# schematic.net
KiCad netlist of a schematic drawn in Altium Designer
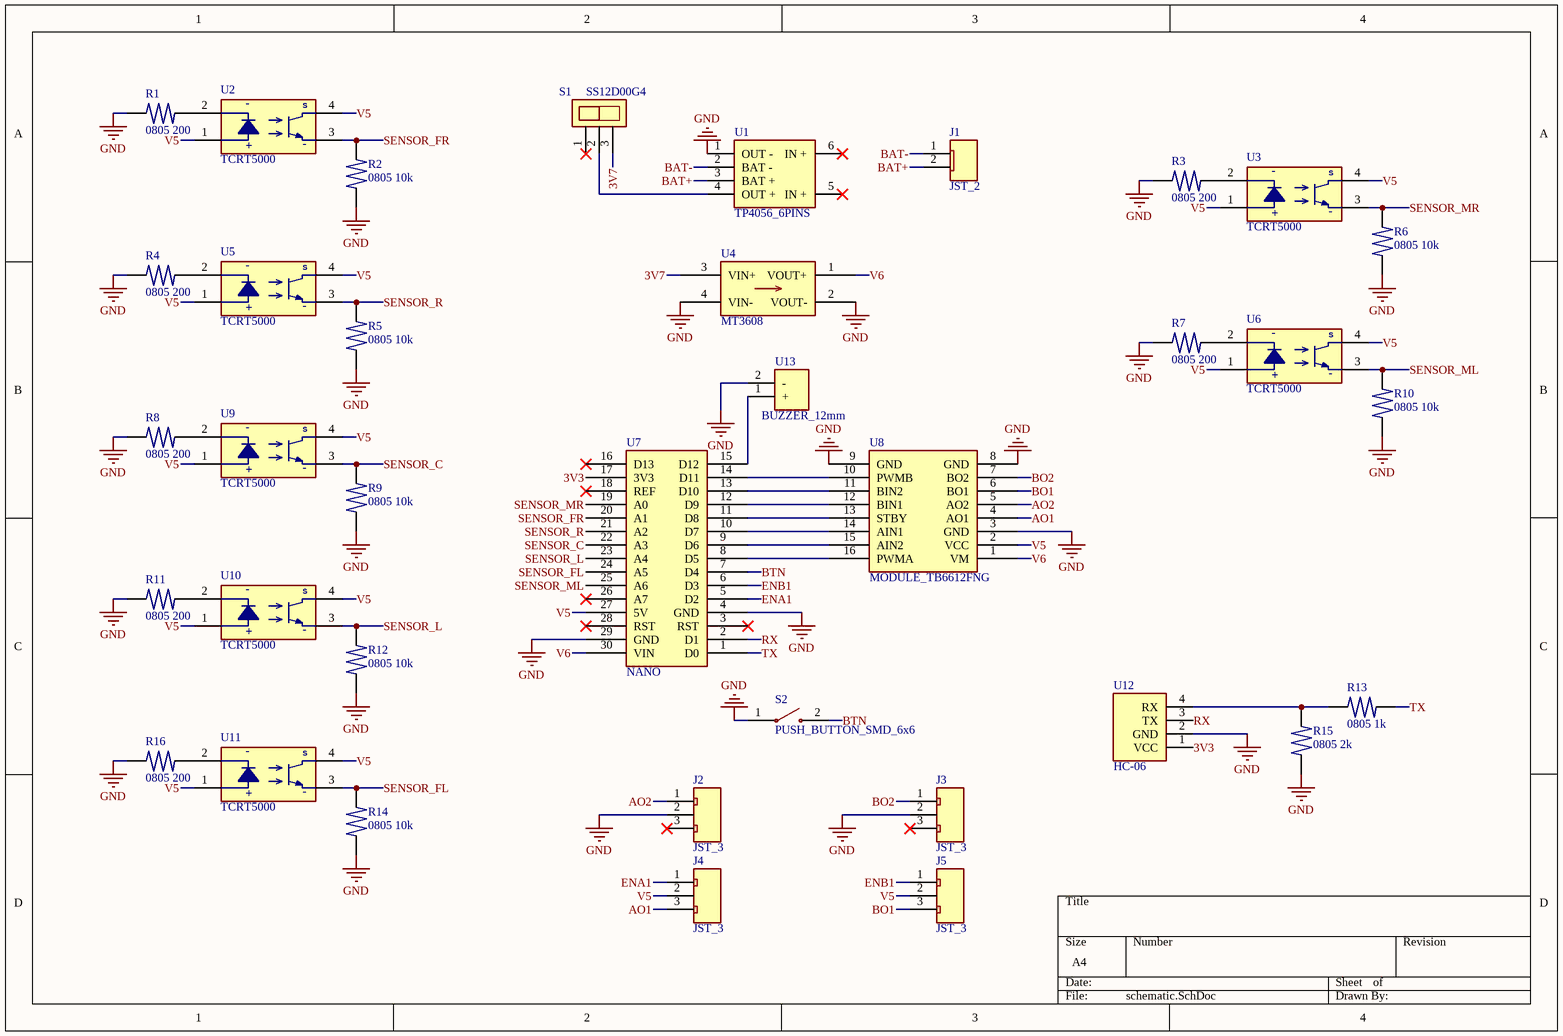
[diagram p0: schematic.SchDoc]

(export (version "E")
  (design (tool "Eeschema 10.0.6"))
  (components
    (comp (ref "J1") (value "JST_2") (footprint "JST_2") (libsource (lib "Connectors") (part "JST_2")))
    (comp (ref "J2") (value "JST_3") (footprint "JST_3") (libsource (lib "Connectors") (part "JST_3")))
    (comp (ref "J3") (value "JST_3") (footprint "JST_3") (libsource (lib "Connectors") (part "JST_3")))
    (comp (ref "J4") (value "JST_3") (footprint "JST_3") (libsource (lib "Connectors") (part "JST_3")))
    (comp (ref "J5") (value "JST_3") (footprint "JST_3") (libsource (lib "Connectors") (part "JST_3")))
    (comp (ref "R1")
      (value "0805 200")
      (footprint "RESISTOR_0805")
      (libsource (lib "Resistors") (part "RESISTOR_0805"))
    )
    (comp (ref "R2")
      (value "0805 10k")
      (footprint "RESISTOR_0805")
      (libsource (lib "Resistors") (part "RESISTOR_0805"))
    )
    (comp (ref "R3")
      (value "0805 200")
      (footprint "RESISTOR_0805")
      (libsource (lib "Resistors") (part "RESISTOR_0805"))
    )
    (comp (ref "R4")
      (value "0805 200")
      (footprint "RESISTOR_0805")
      (libsource (lib "Resistors") (part "RESISTOR_0805"))
    )
    (comp (ref "R5")
      (value "0805 10k")
      (footprint "RESISTOR_0805")
      (libsource (lib "Resistors") (part "RESISTOR_0805"))
    )
    (comp (ref "R6")
      (value "0805 10k")
      (footprint "RESISTOR_0805")
      (libsource (lib "Resistors") (part "RESISTOR_0805"))
    )
    (comp (ref "R7")
      (value "0805 200")
      (footprint "RESISTOR_0805")
      (libsource (lib "Resistors") (part "RESISTOR_0805"))
    )
    (comp (ref "R8")
      (value "0805 200")
      (footprint "RESISTOR_0805")
      (libsource (lib "Resistors") (part "RESISTOR_0805"))
    )
    (comp (ref "R9")
      (value "0805 10k")
      (footprint "RESISTOR_0805")
      (libsource (lib "Resistors") (part "RESISTOR_0805"))
    )
    (comp (ref "R10")
      (value "0805 10k")
      (footprint "RESISTOR_0805")
      (libsource (lib "Resistors") (part "RESISTOR_0805"))
    )
    (comp (ref "R11")
      (value "0805 200")
      (footprint "RESISTOR_0805")
      (libsource (lib "Resistors") (part "RESISTOR_0805"))
    )
    (comp (ref "R12")
      (value "0805 10k")
      (footprint "RESISTOR_0805")
      (libsource (lib "Resistors") (part "RESISTOR_0805"))
    )
    (comp (ref "R13")
      (value "0805 1k")
      (footprint "RESISTOR_0805")
      (libsource (lib "Resistors") (part "RESISTOR_0805"))
    )
    (comp (ref "R14")
      (value "0805 10k")
      (footprint "RESISTOR_0805")
      (libsource (lib "Resistors") (part "RESISTOR_0805"))
    )
    (comp (ref "R15")
      (value "0805 2k")
      (footprint "RESISTOR_0805")
      (libsource (lib "Resistors") (part "RESISTOR_0805"))
    )
    (comp (ref "R16")
      (value "0805 200")
      (footprint "RESISTOR_0805")
      (libsource (lib "Resistors") (part "RESISTOR_0805"))
    )
    (comp (ref "S1")
      (value "SS12D00G4")
      (footprint "SS12D00G4")
      (libsource (lib "Buttons & Switches") (part "SS12D00G4"))
    )
    (comp (ref "S2")
      (value "PUSH_BUTTON_SMD_6x6")
      (footprint "PUSH_BUTTON_SMD_6x6")
      (libsource (lib "Buttons & Switches") (part "PUSH_BUTTON_SMD_6X6"))
    )
    (comp (ref "U1")
      (value "TP4056_6PINS")
      (footprint "TP4056_6PINs")
      (description "MODULE BATTERY CHARGER 6 PINS")
      (libsource (lib "Random") (part "TP4056_6PINS"))
    )
    (comp (ref "U2")
      (value "TCRT5000")
      (footprint "TCRT5000")
      (description "REFLECTIVE OPTICAL SENSOR PTH")
      (libsource (lib "Sensors") (part "TCRT5000"))
    )
    (comp (ref "U3")
      (value "TCRT5000")
      (footprint "TCRT5000")
      (description "REFLECTIVE OPTICAL SENSOR PTH")
      (libsource (lib "Sensors") (part "TCRT5000"))
    )
    (comp (ref "U4")
      (value "MT3608")
      (footprint "MT3608")
      (description "MODULE BUCK STEP UP 2A 37x17mm")
      (libsource (lib "Voltage Regulators") (part "MT3608"))
    )
    (comp (ref "U5")
      (value "TCRT5000")
      (footprint "TCRT5000")
      (description "REFLECTIVE OPTICAL SENSOR PTH")
      (libsource (lib "Sensors") (part "TCRT5000"))
    )
    (comp (ref "U6")
      (value "TCRT5000")
      (footprint "TCRT5000")
      (description "REFLECTIVE OPTICAL SENSOR PTH")
      (libsource (lib "Sensors") (part "TCRT5000"))
    )
    (comp (ref "U7")
      (value "NANO")
      (footprint "NANO")
      (description "Microcontroller Board ATMEGA328P 30 Pins")
      (libsource (lib "Arduino") (part "NANO"))
    )
    (comp (ref "U8")
      (value "MODULE_TB6612FNG")
      (footprint "MODULE_TB6612FNG")
      (description "Module Dual Motor Driver 2.5-13.5V 3.2A Peak 21x18mm")
      (libsource (lib "Motor Drivers") (part "MODULE_TB6612FNG"))
    )
    (comp (ref "U9")
      (value "TCRT5000")
      (footprint "TCRT5000")
      (description "REFLECTIVE OPTICAL SENSOR PTH")
      (libsource (lib "Sensors") (part "TCRT5000"))
    )
    (comp (ref "U10")
      (value "TCRT5000")
      (footprint "TCRT5000")
      (description "REFLECTIVE OPTICAL SENSOR PTH")
      (libsource (lib "Sensors") (part "TCRT5000"))
    )
    (comp (ref "U11")
      (value "TCRT5000")
      (footprint "TCRT5000")
      (description "REFLECTIVE OPTICAL SENSOR PTH")
      (libsource (lib "Sensors") (part "TCRT5000"))
    )
    (comp (ref "U12")
      (value "HC-06")
      (footprint "HC-06")
      (description "BLUETOOTH MODULE")
      (libsource (lib "Communication") (part "HC-06"))
    )
    (comp (ref "U13")
      (value "BUZZER_12mm")
      (footprint "BUZZER_12mm")
      (description "BUZZER MAGNETIC 12MM")
      (libsource (lib "Random") (part "BUZZER_12mm"))
    )
  )
  (nets
    (net (code "1") (name "/3V3") (class "Default")
      (node (ref "U12") (pin "1") (pinfunction "VCC_1") (pintype "passive"))
      (node (ref "U7") (pin "17") (pinfunction "3V3_17") (pintype "passive"))
    )
    (net (code "2") (name "/3V7") (class "Default")
      (node (ref "S1") (pin "3") (pintype "passive"))
      (node (ref "U4") (pin "3") (pinfunction "VIN+_3") (pintype "passive"))
    )
    (net (code "3") (name "/AO1") (class "Default")
      (node (ref "J4") (pin "3") (pintype "passive"))
      (node (ref "U8") (pin "4") (pinfunction "AO1_4") (pintype "passive"))
    )
    (net (code "4") (name "/AO2") (class "Default")
      (node (ref "J2") (pin "1") (pintype "passive"))
      (node (ref "U8") (pin "5") (pinfunction "AO2_5") (pintype "passive"))
    )
    (net (code "5") (name "/BAT+") (class "Default")
      (node (ref "J1") (pin "2") (pintype "passive"))
      (node (ref "U1") (pin "3") (pinfunction "BAT_+_3") (pintype "passive"))
    )
    (net (code "6") (name "/BAT-") (class "Default")
      (node (ref "J1") (pin "1") (pintype "passive"))
      (node (ref "U1") (pin "2") (pinfunction "BAT_-_2") (pintype "passive"))
    )
    (net (code "7") (name "/BO1") (class "Default")
      (node (ref "J5") (pin "3") (pintype "passive"))
      (node (ref "U8") (pin "6") (pinfunction "BO1_6") (pintype "passive"))
    )
    (net (code "8") (name "/BO2") (class "Default")
      (node (ref "J3") (pin "1") (pintype "passive"))
      (node (ref "U8") (pin "7") (pinfunction "BO2_7") (pintype "passive"))
    )
    (net (code "9") (name "/BTN") (class "Default")
      (node (ref "S2") (pin "2") (pinfunction "2_2") (pintype "passive"))
      (node (ref "U7") (pin "7") (pinfunction "D4_7") (pintype "passive"))
    )
    (net (code "10") (name "/ENA1") (class "Default")
      (node (ref "J4") (pin "1") (pintype "passive"))
      (node (ref "U7") (pin "5") (pinfunction "D2_5") (pintype "passive"))
    )
    (net (code "11") (name "/ENB1") (class "Default")
      (node (ref "J5") (pin "1") (pintype "passive"))
      (node (ref "U7") (pin "6") (pinfunction "D3_6") (pintype "passive"))
    )
    (net (code "12") (name "/RX") (class "Default")
      (node (ref "U12") (pin "3") (pinfunction "TX_3") (pintype "passive"))
      (node (ref "U7") (pin "2") (pinfunction "D1_2") (pintype "passive"))
    )
    (net (code "13") (name "/SENSOR_C") (class "Default")
      (node (ref "R9") (pin "2") (pinfunction "2_2") (pintype "passive"))
      (node (ref "U7") (pin "22") (pinfunction "A3_22") (pintype "passive"))
      (node (ref "U9") (pin "3") (pinfunction "GND_3") (pintype "passive"))
    )
    (net (code "14") (name "/SENSOR_FL") (class "Default")
      (node (ref "R14") (pin "2") (pinfunction "2_2") (pintype "passive"))
      (node (ref "U11") (pin "3") (pinfunction "GND_3") (pintype "passive"))
      (node (ref "U7") (pin "24") (pinfunction "A5_24") (pintype "passive"))
    )
    (net (code "15") (name "/SENSOR_FR") (class "Default")
      (node (ref "R2") (pin "2") (pinfunction "2_2") (pintype "passive"))
      (node (ref "U2") (pin "3") (pinfunction "GND_3") (pintype "passive"))
      (node (ref "U7") (pin "20") (pinfunction "A1_20") (pintype "passive"))
    )
    (net (code "16") (name "/SENSOR_L") (class "Default")
      (node (ref "R12") (pin "2") (pinfunction "2_2") (pintype "passive"))
      (node (ref "U10") (pin "3") (pinfunction "GND_3") (pintype "passive"))
      (node (ref "U7") (pin "23") (pinfunction "A4_23") (pintype "passive"))
    )
    (net (code "17") (name "/SENSOR_ML") (class "Default")
      (node (ref "R10") (pin "2") (pinfunction "2_2") (pintype "passive"))
      (node (ref "U6") (pin "3") (pinfunction "GND_3") (pintype "passive"))
      (node (ref "U7") (pin "25") (pinfunction "A6_25") (pintype "passive"))
    )
    (net (code "18") (name "/SENSOR_MR") (class "Default")
      (node (ref "R6") (pin "2") (pinfunction "2_2") (pintype "passive"))
      (node (ref "U3") (pin "3") (pinfunction "GND_3") (pintype "passive"))
      (node (ref "U7") (pin "19") (pinfunction "A0_19") (pintype "passive"))
    )
    (net (code "19") (name "/SENSOR_R") (class "Default")
      (node (ref "R5") (pin "2") (pinfunction "2_2") (pintype "passive"))
      (node (ref "U5") (pin "3") (pinfunction "GND_3") (pintype "passive"))
      (node (ref "U7") (pin "21") (pinfunction "A2_21") (pintype "passive"))
    )
    (net (code "20") (name "/TX") (class "Default")
      (node (ref "R13") (pin "2") (pinfunction "2_2") (pintype "passive"))
      (node (ref "U7") (pin "1") (pinfunction "D0_1") (pintype "passive"))
    )
    (net (code "21") (name "/V5") (class "Default")
      (node (ref "J4") (pin "2") (pintype "passive"))
      (node (ref "J5") (pin "2") (pintype "passive"))
      (node (ref "U10") (pin "1") (pinfunction "VCC_1") (pintype "passive"))
      (node (ref "U10") (pin "4") (pinfunction "SIGNAL_4") (pintype "passive"))
      (node (ref "U11") (pin "1") (pinfunction "VCC_1") (pintype "passive"))
      (node (ref "U11") (pin "4") (pinfunction "SIGNAL_4") (pintype "passive"))
      (node (ref "U2") (pin "1") (pinfunction "VCC_1") (pintype "passive"))
      (node (ref "U2") (pin "4") (pinfunction "SIGNAL_4") (pintype "passive"))
      (node (ref "U3") (pin "1") (pinfunction "VCC_1") (pintype "passive"))
      (node (ref "U3") (pin "4") (pinfunction "SIGNAL_4") (pintype "passive"))
      (node (ref "U5") (pin "1") (pinfunction "VCC_1") (pintype "passive"))
      (node (ref "U5") (pin "4") (pinfunction "SIGNAL_4") (pintype "passive"))
      (node (ref "U6") (pin "1") (pinfunction "VCC_1") (pintype "passive"))
      (node (ref "U6") (pin "4") (pinfunction "SIGNAL_4") (pintype "passive"))
      (node (ref "U7") (pin "27") (pinfunction "5V_27") (pintype "passive"))
      (node (ref "U8") (pin "2") (pinfunction "VCC_2") (pintype "passive"))
      (node (ref "U9") (pin "1") (pinfunction "VCC_1") (pintype "passive"))
      (node (ref "U9") (pin "4") (pinfunction "SIGNAL_4") (pintype "passive"))
    )
    (net (code "22") (name "/V6") (class "Default")
      (node (ref "U4") (pin "1") (pinfunction "VOUT+_1") (pintype "passive"))
      (node (ref "U7") (pin "30") (pinfunction "VIN_30") (pintype "passive"))
      (node (ref "U8") (pin "1") (pinfunction "VM_1") (pintype "passive"))
    )
    (net (code "23") (name "GND") (class "Default")
      (node (ref "J2") (pin "2") (pintype "passive"))
      (node (ref "J3") (pin "2") (pintype "passive"))
      (node (ref "R1") (pin "1") (pinfunction "1_1") (pintype "passive"))
      (node (ref "R10") (pin "1") (pinfunction "1_1") (pintype "passive"))
      (node (ref "R11") (pin "1") (pinfunction "1_1") (pintype "passive"))
      (node (ref "R12") (pin "1") (pinfunction "1_1") (pintype "passive"))
      (node (ref "R14") (pin "1") (pinfunction "1_1") (pintype "passive"))
      (node (ref "R15") (pin "1") (pinfunction "1_1") (pintype "passive"))
      (node (ref "R16") (pin "1") (pinfunction "1_1") (pintype "passive"))
      (node (ref "R2") (pin "1") (pinfunction "1_1") (pintype "passive"))
      (node (ref "R3") (pin "1") (pinfunction "1_1") (pintype "passive"))
      (node (ref "R4") (pin "1") (pinfunction "1_1") (pintype "passive"))
      (node (ref "R5") (pin "1") (pinfunction "1_1") (pintype "passive"))
      (node (ref "R6") (pin "1") (pinfunction "1_1") (pintype "passive"))
      (node (ref "R7") (pin "1") (pinfunction "1_1") (pintype "passive"))
      (node (ref "R8") (pin "1") (pinfunction "1_1") (pintype "passive"))
      (node (ref "R9") (pin "1") (pinfunction "1_1") (pintype "passive"))
      (node (ref "S2") (pin "1") (pinfunction "1_1") (pintype "passive"))
      (node (ref "U1") (pin "1") (pinfunction "OUT_-_1") (pintype "passive"))
      (node (ref "U12") (pin "2") (pinfunction "GND_2") (pintype "passive"))
      (node (ref "U13") (pin "2") (pinfunction "-_2") (pintype "passive"))
      (node (ref "U4") (pin "2") (pinfunction "VOUT-_2") (pintype "passive"))
      (node (ref "U4") (pin "4") (pinfunction "VIN-_4") (pintype "passive"))
      (node (ref "U7") (pin "29") (pinfunction "GND_29") (pintype "passive"))
      (node (ref "U7") (pin "4") (pinfunction "GND_4") (pintype "passive"))
      (node (ref "U8") (pin "3") (pinfunction "GND_3") (pintype "passive"))
      (node (ref "U8") (pin "8") (pinfunction "GND_8") (pintype "passive"))
      (node (ref "U8") (pin "9") (pinfunction "GND_9") (pintype "passive"))
    )
    (net (code "24") (name "Net-(R1-Pad2)") (class "Default")
      (node (ref "R1") (pin "2") (pinfunction "2_2") (pintype "passive"))
      (node (ref "U2") (pin "2") (pinfunction "GND_2") (pintype "passive"))
    )
    (net (code "25") (name "Net-(R3-Pad2)") (class "Default")
      (node (ref "R3") (pin "2") (pinfunction "2_2") (pintype "passive"))
      (node (ref "U3") (pin "2") (pinfunction "GND_2") (pintype "passive"))
    )
    (net (code "26") (name "Net-(R4-Pad2)") (class "Default")
      (node (ref "R4") (pin "2") (pinfunction "2_2") (pintype "passive"))
      (node (ref "U5") (pin "2") (pinfunction "GND_2") (pintype "passive"))
    )
    (net (code "27") (name "Net-(R7-Pad2)") (class "Default")
      (node (ref "R7") (pin "2") (pinfunction "2_2") (pintype "passive"))
      (node (ref "U6") (pin "2") (pinfunction "GND_2") (pintype "passive"))
    )
    (net (code "28") (name "Net-(R8-Pad2)") (class "Default")
      (node (ref "R8") (pin "2") (pinfunction "2_2") (pintype "passive"))
      (node (ref "U9") (pin "2") (pinfunction "GND_2") (pintype "passive"))
    )
    (net (code "29") (name "Net-(R11-Pad2)") (class "Default")
      (node (ref "R11") (pin "2") (pinfunction "2_2") (pintype "passive"))
      (node (ref "U10") (pin "2") (pinfunction "GND_2") (pintype "passive"))
    )
    (net (code "30") (name "Net-(R16-Pad2)") (class "Default")
      (node (ref "R16") (pin "2") (pinfunction "2_2") (pintype "passive"))
      (node (ref "U11") (pin "2") (pinfunction "GND_2") (pintype "passive"))
    )
    (net (code "31") (name "Net-(U1-OUT_+)") (class "Default")
      (node (ref "S1") (pin "2") (pintype "passive"))
      (node (ref "U1") (pin "4") (pinfunction "OUT_+_4") (pintype "passive"))
    )
    (net (code "32") (name "Net-(U7-D5)") (class "Default")
      (node (ref "U7") (pin "8") (pinfunction "D5_8") (pintype "passive"))
      (node (ref "U8") (pin "16") (pinfunction "PWMA_16") (pintype "passive"))
    )
    (net (code "33") (name "Net-(U7-D6)") (class "Default")
      (node (ref "U7") (pin "9") (pinfunction "D6_9") (pintype "passive"))
      (node (ref "U8") (pin "15") (pinfunction "AIN2_15") (pintype "passive"))
    )
    (net (code "34") (name "Net-(U7-D7)") (class "Default")
      (node (ref "U7") (pin "10") (pinfunction "D7_10") (pintype "passive"))
      (node (ref "U8") (pin "14") (pinfunction "AIN1_14") (pintype "passive"))
    )
    (net (code "35") (name "Net-(U7-D8)") (class "Default")
      (node (ref "U7") (pin "11") (pinfunction "D8_11") (pintype "passive"))
      (node (ref "U8") (pin "13") (pinfunction "STBY_13") (pintype "passive"))
    )
    (net (code "36") (name "Net-(U7-D9)") (class "Default")
      (node (ref "U7") (pin "12") (pinfunction "D9_12") (pintype "passive"))
      (node (ref "U8") (pin "12") (pinfunction "BIN1_12") (pintype "passive"))
    )
    (net (code "37") (name "Net-(U7-D10)") (class "Default")
      (node (ref "U7") (pin "13") (pinfunction "D10_13") (pintype "passive"))
      (node (ref "U8") (pin "11") (pinfunction "BIN2_11") (pintype "passive"))
    )
    (net (code "38") (name "Net-(U7-D11)") (class "Default")
      (node (ref "U7") (pin "14") (pinfunction "D11_14") (pintype "passive"))
      (node (ref "U8") (pin "10") (pinfunction "PWMB_10") (pintype "passive"))
    )
    (net (code "39") (name "Net-(U12-RX)") (class "Default")
      (node (ref "R13") (pin "1") (pinfunction "1_1") (pintype "passive"))
      (node (ref "R15") (pin "2") (pinfunction "2_2") (pintype "passive"))
      (node (ref "U12") (pin "4") (pinfunction "RX_4") (pintype "passive"))
    )
    (net (code "40") (name "Net-(U13-+)") (class "Default")
      (node (ref "U13") (pin "1") (pinfunction "+_1") (pintype "passive"))
      (node (ref "U7") (pin "15") (pinfunction "D12_15") (pintype "passive"))
    )
    (net (code "41") (name "unconnected-(J2-Pad3)") (class "Default")
      (node (ref "J2") (pin "3") (pintype "passive+no_connect"))
    )
    (net (code "42") (name "unconnected-(J3-Pad3)") (class "Default")
      (node (ref "J3") (pin "3") (pintype "passive+no_connect"))
    )
    (net (code "43") (name "unconnected-(S1-Pad1)") (class "Default")
      (node (ref "S1") (pin "1") (pintype "passive+no_connect"))
    )
    (net (code "44") (name "unconnected-(U1-IN_+-Pad5)") (class "Default")
      (node (ref "U1") (pin "5") (pinfunction "IN_+_5") (pintype "passive+no_connect"))
    )
    (net (code "45") (name "unconnected-(U1-IN_+-Pad6)") (class "Default")
      (node (ref "U1") (pin "6") (pinfunction "IN_+_6") (pintype "passive+no_connect"))
    )
    (net (code "46") (name "unconnected-(U7-A7-Pad26)") (class "Default")
      (node (ref "U7") (pin "26") (pinfunction "A7_26") (pintype "passive+no_connect"))
    )
    (net (code "47") (name "unconnected-(U7-D13-Pad16)") (class "Default")
      (node (ref "U7") (pin "16") (pinfunction "D13_16") (pintype "passive+no_connect"))
    )
    (net (code "48") (name "unconnected-(U7-REF-Pad18)") (class "Default")
      (node (ref "U7") (pin "18") (pinfunction "REF_18") (pintype "passive+no_connect"))
    )
    (net (code "49") (name "unconnected-(U7-RST-Pad3)") (class "Default")
      (node (ref "U7") (pin "3") (pinfunction "RST_3") (pintype "passive+no_connect"))
    )
    (net (code "50") (name "unconnected-(U7-RST-Pad28)") (class "Default")
      (node (ref "U7") (pin "28") (pinfunction "RST_28") (pintype "passive+no_connect"))
    )
  )
)
